# Final_flipped_Schematic_model.net
KiCad netlist of a schematic drawn in EAGLE
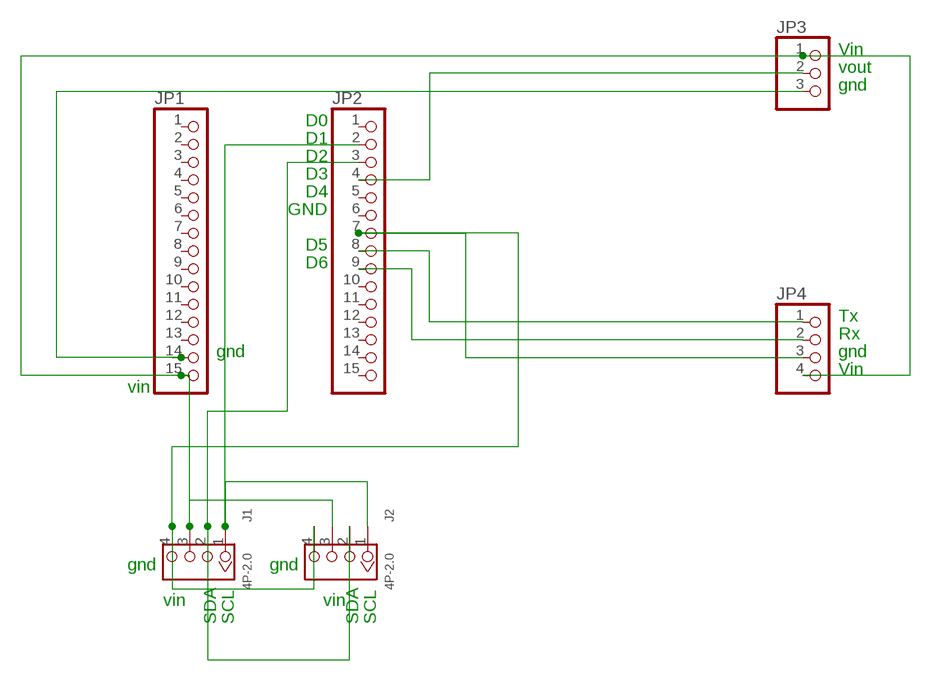
[diagram p0: schematic, sheet 1]

(export (version "E")
  (design (tool "Eeschema 10.0.6"))
  (components
    (comp (ref "J1")
      (value "4P-2.0")
      (footprint "eagle-import:HW4-2.0")
      (libsource (lib "eagle-import") (part "GROVE-CONNECTOR-DIP(4P-2.0)"))
    )
    (comp (ref "J2")
      (value "4P-2.0")
      (footprint "eagle-import:HW4-2.0")
      (libsource (lib "eagle-import") (part "GROVE-CONNECTOR-DIP(4P-2.0)"))
    )
    (comp (ref "JP1")
      (value "PINHD-1X15")
      (footprint "eagle-import:1X15")
      (libsource (lib "eagle-import") (part "PINHD-1X15"))
    )
    (comp (ref "JP2")
      (value "PINHD-1X15")
      (footprint "eagle-import:1X15")
      (libsource (lib "eagle-import") (part "PINHD-1X15"))
    )
    (comp (ref "JP3")
      (value "PINHD-1X3")
      (footprint "eagle-import:1X03")
      (libsource (lib "eagle-import") (part "PINHD-1X3"))
    )
    (comp (ref "JP4")
      (value "PINHD-1X4")
      (footprint "eagle-import:1X04")
      (libsource (lib "eagle-import") (part "PINHD-1X4"))
    )
  )
  (nets
    (net (code "1") (name "Net-(J1-Pad1)") (class "Default")
      (node (ref "J1") (pin "1") (pinfunction "1_1") (pintype "bidirectional"))
      (node (ref "J2") (pin "1") (pinfunction "1_1") (pintype "bidirectional"))
      (node (ref "JP2") (pin "2") (pinfunction "2_2") (pintype "passive"))
    )
    (net (code "2") (name "Net-(J1-Pad2)") (class "Default")
      (node (ref "J1") (pin "2") (pinfunction "2_2") (pintype "bidirectional"))
      (node (ref "J2") (pin "2") (pinfunction "2_2") (pintype "bidirectional"))
      (node (ref "JP2") (pin "3") (pinfunction "3_3") (pintype "passive"))
    )
    (net (code "3") (name "Net-(J1-Pad3)") (class "Default")
      (node (ref "J1") (pin "3") (pinfunction "3_3") (pintype "bidirectional"))
      (node (ref "J2") (pin "3") (pinfunction "3_3") (pintype "bidirectional"))
      (node (ref "JP1") (pin "15") (pinfunction "15_15") (pintype "passive"))
      (node (ref "JP3") (pin "1") (pinfunction "1_1") (pintype "passive"))
      (node (ref "JP4") (pin "4") (pinfunction "4_4") (pintype "passive"))
    )
    (net (code "4") (name "Net-(J1-Pad4)") (class "Default")
      (node (ref "J1") (pin "4") (pinfunction "4_4") (pintype "bidirectional"))
      (node (ref "J2") (pin "4") (pinfunction "4_4") (pintype "bidirectional"))
      (node (ref "JP2") (pin "7") (pinfunction "7_7") (pintype "passive"))
      (node (ref "JP4") (pin "3") (pinfunction "3_3") (pintype "passive"))
    )
    (net (code "5") (name "Net-(JP1-Pad14)") (class "Default")
      (node (ref "JP1") (pin "14") (pinfunction "14_14") (pintype "passive"))
      (node (ref "JP3") (pin "3") (pinfunction "3_3") (pintype "passive"))
    )
    (net (code "6") (name "Net-(JP2-Pad4)") (class "Default")
      (node (ref "JP2") (pin "4") (pinfunction "4_4") (pintype "passive"))
      (node (ref "JP3") (pin "2") (pinfunction "2_2") (pintype "passive"))
    )
    (net (code "7") (name "Net-(JP2-Pad8)") (class "Default")
      (node (ref "JP2") (pin "8") (pinfunction "8_8") (pintype "passive"))
      (node (ref "JP4") (pin "1") (pinfunction "1_1") (pintype "passive"))
    )
    (net (code "8") (name "Net-(JP2-Pad9)") (class "Default")
      (node (ref "JP2") (pin "9") (pinfunction "9_9") (pintype "passive"))
      (node (ref "JP4") (pin "2") (pinfunction "2_2") (pintype "passive"))
    )
    (net (code "9") (name "unconnected-(JP1-Pad1)") (class "Default")
      (node (ref "JP1") (pin "1") (pinfunction "1_1") (pintype "passive"))
    )
    (net (code "10") (name "unconnected-(JP1-Pad2)") (class "Default")
      (node (ref "JP1") (pin "2") (pinfunction "2_2") (pintype "passive"))
    )
    (net (code "11") (name "unconnected-(JP1-Pad3)") (class "Default")
      (node (ref "JP1") (pin "3") (pinfunction "3_3") (pintype "passive"))
    )
    (net (code "12") (name "unconnected-(JP1-Pad4)") (class "Default")
      (node (ref "JP1") (pin "4") (pinfunction "4_4") (pintype "passive"))
    )
    (net (code "13") (name "unconnected-(JP1-Pad5)") (class "Default")
      (node (ref "JP1") (pin "5") (pinfunction "5_5") (pintype "passive"))
    )
    (net (code "14") (name "unconnected-(JP1-Pad6)") (class "Default")
      (node (ref "JP1") (pin "6") (pinfunction "6_6") (pintype "passive"))
    )
    (net (code "15") (name "unconnected-(JP1-Pad7)") (class "Default")
      (node (ref "JP1") (pin "7") (pinfunction "7_7") (pintype "passive"))
    )
    (net (code "16") (name "unconnected-(JP1-Pad8)") (class "Default")
      (node (ref "JP1") (pin "8") (pinfunction "8_8") (pintype "passive"))
    )
    (net (code "17") (name "unconnected-(JP1-Pad9)") (class "Default")
      (node (ref "JP1") (pin "9") (pinfunction "9_9") (pintype "passive"))
    )
    (net (code "18") (name "unconnected-(JP1-Pad10)") (class "Default")
      (node (ref "JP1") (pin "10") (pinfunction "10_10") (pintype "passive"))
    )
    (net (code "19") (name "unconnected-(JP1-Pad11)") (class "Default")
      (node (ref "JP1") (pin "11") (pinfunction "11_11") (pintype "passive"))
    )
    (net (code "20") (name "unconnected-(JP1-Pad12)") (class "Default")
      (node (ref "JP1") (pin "12") (pinfunction "12_12") (pintype "passive"))
    )
    (net (code "21") (name "unconnected-(JP1-Pad13)") (class "Default")
      (node (ref "JP1") (pin "13") (pinfunction "13_13") (pintype "passive"))
    )
    (net (code "22") (name "unconnected-(JP2-Pad1)") (class "Default")
      (node (ref "JP2") (pin "1") (pinfunction "1_1") (pintype "passive"))
    )
    (net (code "23") (name "unconnected-(JP2-Pad5)") (class "Default")
      (node (ref "JP2") (pin "5") (pinfunction "5_5") (pintype "passive"))
    )
    (net (code "24") (name "unconnected-(JP2-Pad6)") (class "Default")
      (node (ref "JP2") (pin "6") (pinfunction "6_6") (pintype "passive"))
    )
    (net (code "25") (name "unconnected-(JP2-Pad10)") (class "Default")
      (node (ref "JP2") (pin "10") (pinfunction "10_10") (pintype "passive"))
    )
    (net (code "26") (name "unconnected-(JP2-Pad11)") (class "Default")
      (node (ref "JP2") (pin "11") (pinfunction "11_11") (pintype "passive"))
    )
    (net (code "27") (name "unconnected-(JP2-Pad12)") (class "Default")
      (node (ref "JP2") (pin "12") (pinfunction "12_12") (pintype "passive"))
    )
    (net (code "28") (name "unconnected-(JP2-Pad13)") (class "Default")
      (node (ref "JP2") (pin "13") (pinfunction "13_13") (pintype "passive"))
    )
    (net (code "29") (name "unconnected-(JP2-Pad14)") (class "Default")
      (node (ref "JP2") (pin "14") (pinfunction "14_14") (pintype "passive"))
    )
    (net (code "30") (name "unconnected-(JP2-Pad15)") (class "Default")
      (node (ref "JP2") (pin "15") (pinfunction "15_15") (pintype "passive"))
    )
  )
)
